# bs_prod.net
KiCad netlist of a schematic drawn in EAGLE
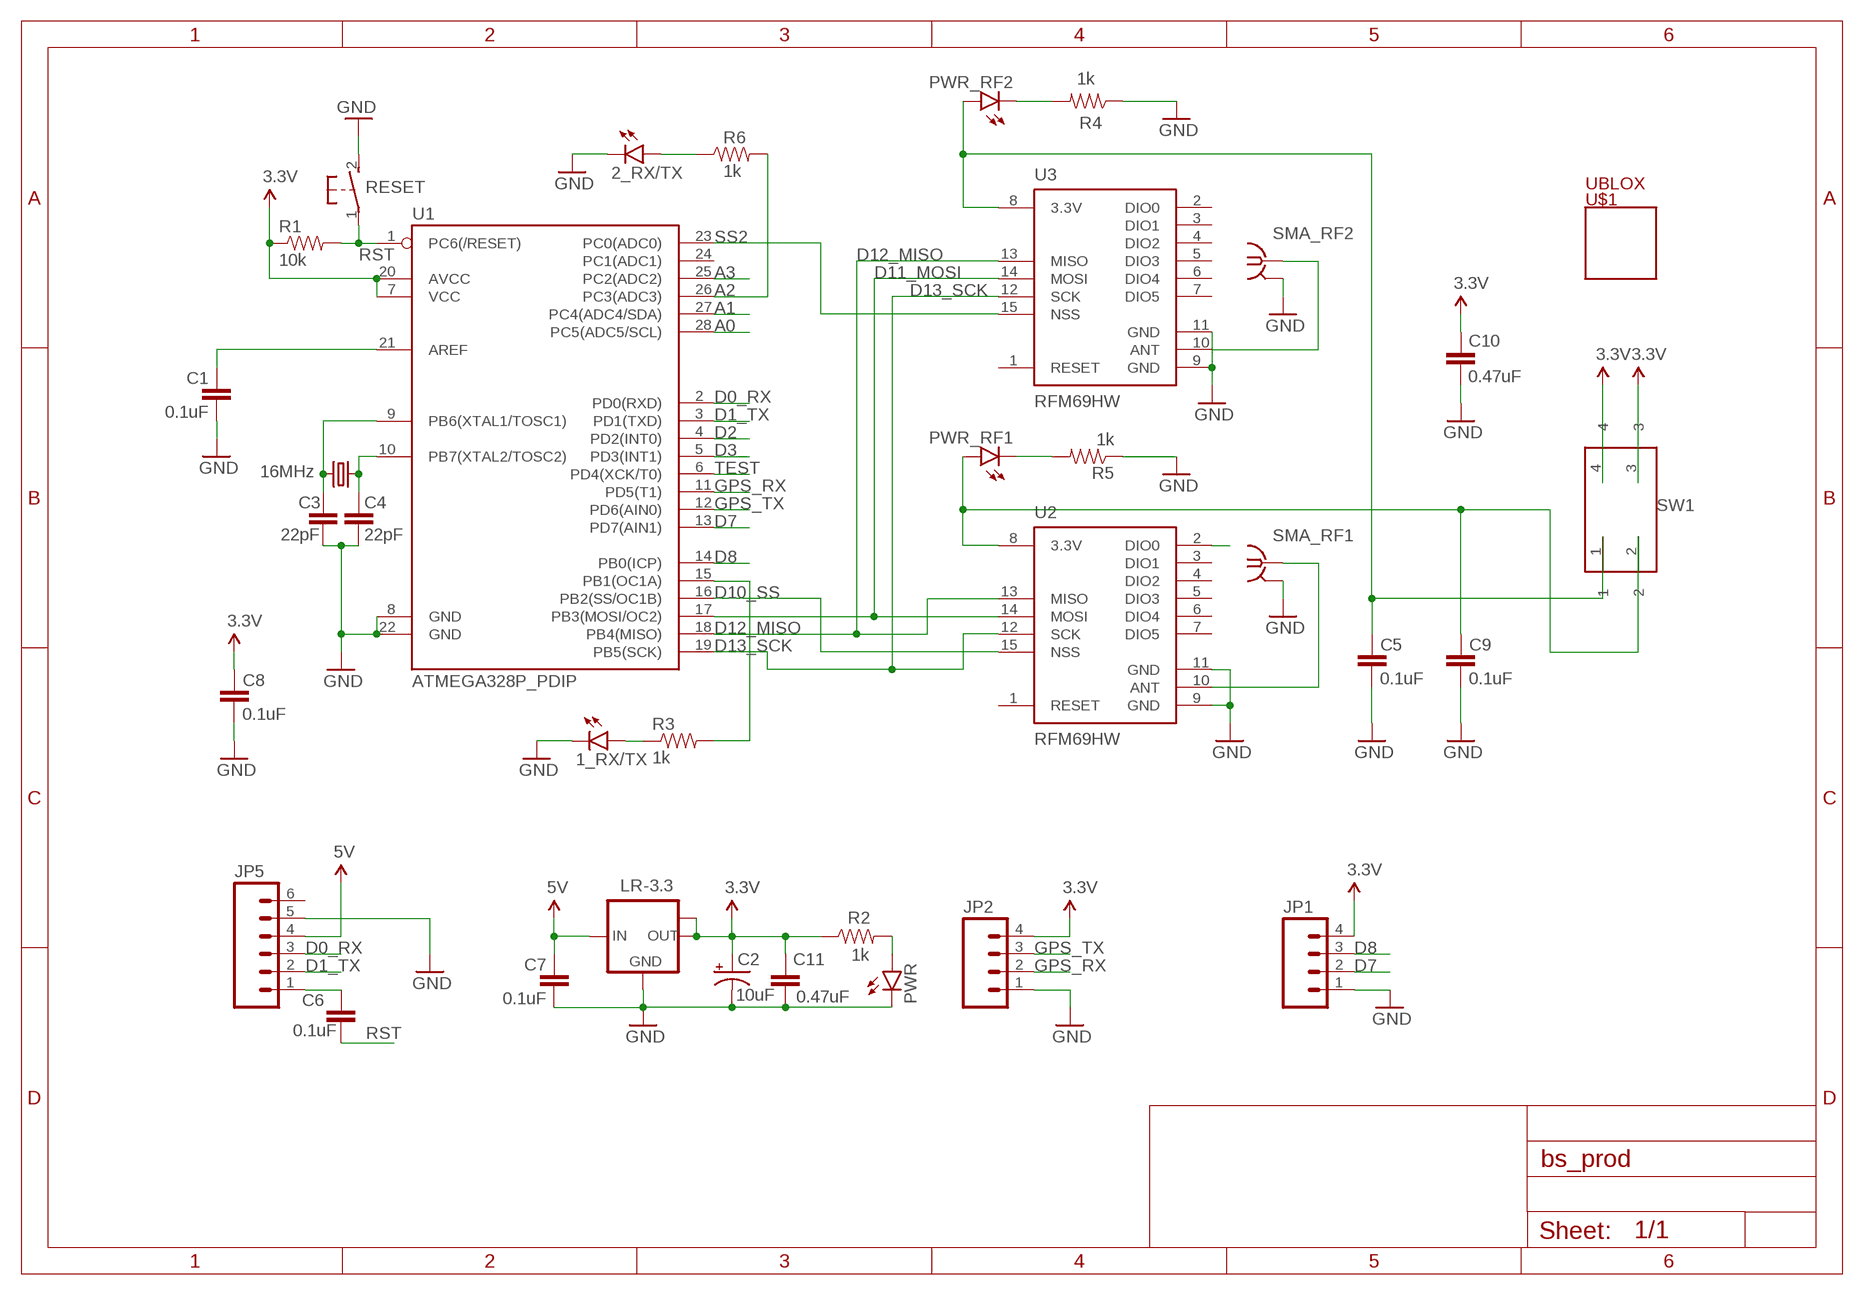
[diagram p0: schematic, sheet 1]

(export (version "E")
  (design (tool "Eeschema 10.0.6"))
  (components
    (comp (ref "1_RX/TX")
      (value "LED1206")
      (footprint "eagle-import:LED-1206")
      (libsource (lib "eagle-import") (part "LED1206"))
    )
    (comp (ref "2_RX/TX")
      (value "LED1206")
      (footprint "eagle-import:LED-1206")
      (libsource (lib "eagle-import") (part "LED1206"))
    )
    (comp (ref "C1")
      (value "0.1uF")
      (footprint "eagle-import:1206")
      (libsource (lib "eagle-import") (part "CAP1206"))
    )
    (comp (ref "C2")
      (value "10uF")
      (footprint "eagle-import:PANASONIC_C")
      (libsource (lib "eagle-import") (part "CAP_POLC"))
    )
    (comp (ref "C3")
      (value "22pF")
      (footprint "eagle-import:1206")
      (libsource (lib "eagle-import") (part "CAP1206"))
    )
    (comp (ref "C4")
      (value "22pF")
      (footprint "eagle-import:1206")
      (libsource (lib "eagle-import") (part "CAP1206"))
    )
    (comp (ref "C5")
      (value "0.1uF")
      (footprint "eagle-import:1206")
      (libsource (lib "eagle-import") (part "CAP1206"))
    )
    (comp (ref "C6")
      (value "0.1uF")
      (footprint "eagle-import:1206")
      (libsource (lib "eagle-import") (part "CAP1206"))
    )
    (comp (ref "C7")
      (value "0.1uF")
      (footprint "eagle-import:1206")
      (libsource (lib "eagle-import") (part "CAP1206"))
    )
    (comp (ref "C8")
      (value "0.1uF")
      (footprint "eagle-import:1206")
      (libsource (lib "eagle-import") (part "CAP1206"))
    )
    (comp (ref "C9")
      (value "0.1uF")
      (footprint "eagle-import:1206")
      (libsource (lib "eagle-import") (part "CAP1206"))
    )
    (comp (ref "C10")
      (value "0.47uF")
      (footprint "eagle-import:1206")
      (libsource (lib "eagle-import") (part "CAP1206"))
    )
    (comp (ref "C11")
      (value "0.47uF")
      (footprint "eagle-import:1206")
      (libsource (lib "eagle-import") (part "CAP1206"))
    )
    (comp (ref "JP1")
      (value "M04PTH")
      (footprint "eagle-import:1X04")
      (libsource (lib "eagle-import") (part "M04PTH"))
    )
    (comp (ref "JP2")
      (value "M04PTH")
      (footprint "eagle-import:1X04")
      (libsource (lib "eagle-import") (part "M04PTH"))
    )
    (comp (ref "JP5")
      (value "M06SIP")
      (footprint "eagle-import:1X06")
      (libsource (lib "eagle-import") (part "M06SIP"))
    )
    (comp (ref "LR-3.3")
      (value "LM1117IMPX-3.3")
      (footprint "eagle-import:SOT223")
      (libsource (lib "eagle-import") (part "LM1117IMPX-3.3"))
    )
    (comp (ref "PWR")
      (value "LED1206")
      (footprint "eagle-import:LED-1206")
      (libsource (lib "eagle-import") (part "LED1206"))
    )
    (comp (ref "PWR_RF1")
      (value "LED1206")
      (footprint "eagle-import:LED-1206")
      (libsource (lib "eagle-import") (part "LED1206"))
    )
    (comp (ref "PWR_RF2")
      (value "LED1206")
      (footprint "eagle-import:LED-1206")
      (libsource (lib "eagle-import") (part "LED1206"))
    )
    (comp (ref "R1")
      (value "10k")
      (footprint "eagle-import:1206")
      (libsource (lib "eagle-import") (part "RESISTOR1206"))
    )
    (comp (ref "R2")
      (value "1k")
      (footprint "eagle-import:1206")
      (libsource (lib "eagle-import") (part "RESISTOR1206"))
    )
    (comp (ref "R3")
      (value "1k")
      (footprint "eagle-import:1206")
      (libsource (lib "eagle-import") (part "RESISTOR1206"))
    )
    (comp (ref "R4")
      (value "1k")
      (footprint "eagle-import:1206")
      (libsource (lib "eagle-import") (part "RESISTOR1206"))
    )
    (comp (ref "R5")
      (value "1k")
      (footprint "eagle-import:1206")
      (libsource (lib "eagle-import") (part "RESISTOR1206"))
    )
    (comp (ref "R6")
      (value "1k")
      (footprint "eagle-import:1206")
      (libsource (lib "eagle-import") (part "RESISTOR1206"))
    )
    (comp (ref "RESET")
      (value "DTSM-3")
      (footprint "eagle-import:DTSM-3")
      (libsource (lib "eagle-import") (part "DTSM-3"))
    )
    (comp (ref "SMA_RF1")
      (value "BU-SMC-V")
      (footprint "eagle-import:BU-SMC-V")
      (libsource (lib "eagle-import") (part "BU-SMC-V"))
    )
    (comp (ref "SMA_RF2")
      (value "BU-SMC-V")
      (footprint "eagle-import:BU-SMC-V")
      (libsource (lib "eagle-import") (part "BU-SMC-V"))
    )
    (comp (ref "SW1")
      (value "418117270902")
      (footprint "eagle-import:418117270902")
      (libsource (lib "eagle-import") (part "418117270902"))
    )
    (comp (ref "U$1")
      (value "UBLOX")
      (footprint "eagle-import:UBLOX")
      (libsource (lib "eagle-import") (part "UBLOX"))
    )
    (comp (ref "U1")
      (value "ATMEGA328P_PDIP")
      (footprint "eagle-import:DIL28-3")
      (libsource (lib "eagle-import") (part "ATMEGA328P_PDIP"))
    )
    (comp (ref "U2")
      (value "RFM69HW")
      (footprint "eagle-import:RFM69W-XXXS2")
      (libsource (lib "eagle-import") (part "RFM69HW"))
    )
    (comp (ref "U3")
      (value "RFM69HW")
      (footprint "eagle-import:RFM69W-XXXS2")
      (libsource (lib "eagle-import") (part "RFM69HW"))
    )
    (comp (ref "Y1")
      (value "16MHz")
      (footprint "eagle-import:HC49UP")
      (libsource (lib "eagle-import") (part "CRYSTALSMD"))
    )
  )
  (nets
    (net (code "1") (name "/A0") (class "Default")
      (node (ref "U1") (pin "28") (pinfunction "PC5(ADC5/SCL)_28") (pintype "bidirectional"))
    )
    (net (code "2") (name "/A1") (class "Default")
      (node (ref "U1") (pin "27") (pinfunction "PC4(ADC4/SDA)_27") (pintype "bidirectional"))
    )
    (net (code "3") (name "/A2") (class "Default")
      (node (ref "R6") (pin "2") (pinfunction "2_2") (pintype "passive"))
      (node (ref "U1") (pin "26") (pinfunction "PC3(ADC3)_26") (pintype "bidirectional"))
    )
    (net (code "4") (name "/A3") (class "Default")
      (node (ref "U1") (pin "25") (pinfunction "PC2(ADC2)_25") (pintype "bidirectional"))
    )
    (net (code "5") (name "/D0_RX") (class "Default")
      (node (ref "JP5") (pin "3") (pinfunction "3_3") (pintype "passive"))
      (node (ref "U1") (pin "2") (pinfunction "PD0(RXD)_2") (pintype "bidirectional"))
    )
    (net (code "6") (name "/D1_TX") (class "Default")
      (node (ref "JP5") (pin "2") (pinfunction "2_2") (pintype "passive"))
      (node (ref "U1") (pin "3") (pinfunction "PD1(TXD)_3") (pintype "bidirectional"))
    )
    (net (code "7") (name "/D2") (class "Default")
      (node (ref "U1") (pin "4") (pinfunction "PD2(INT0)_4") (pintype "bidirectional"))
    )
    (net (code "8") (name "/D3") (class "Default")
      (node (ref "U1") (pin "5") (pinfunction "PD3(INT1)_5") (pintype "bidirectional"))
    )
    (net (code "9") (name "/D7") (class "Default")
      (node (ref "JP1") (pin "2") (pinfunction "2_2") (pintype "passive"))
      (node (ref "U1") (pin "13") (pinfunction "PD7(AIN1)_13") (pintype "bidirectional"))
    )
    (net (code "10") (name "/D8") (class "Default")
      (node (ref "JP1") (pin "3") (pinfunction "3_3") (pintype "passive"))
      (node (ref "U1") (pin "14") (pinfunction "PB0(ICP)_14") (pintype "bidirectional"))
    )
    (net (code "11") (name "/D10_SS") (class "Default")
      (node (ref "U1") (pin "16") (pinfunction "PB2(SS/OC1B)_16") (pintype "bidirectional"))
      (node (ref "U2") (pin "15") (pinfunction "NSS_15") (pintype "input"))
    )
    (net (code "12") (name "/D11_MOSI") (class "Default")
      (node (ref "U1") (pin "17") (pinfunction "PB3(MOSI/OC2)_17") (pintype "bidirectional"))
      (node (ref "U2") (pin "14") (pinfunction "MOSI_14") (pintype "input"))
      (node (ref "U3") (pin "14") (pinfunction "MOSI_14") (pintype "input"))
    )
    (net (code "13") (name "/D12_MISO") (class "Default")
      (node (ref "U1") (pin "18") (pinfunction "PB4(MISO)_18") (pintype "bidirectional"))
      (node (ref "U2") (pin "13") (pinfunction "MISO_13") (pintype "bidirectional"))
      (node (ref "U3") (pin "13") (pinfunction "MISO_13") (pintype "bidirectional"))
    )
    (net (code "14") (name "/D13_SCK") (class "Default")
      (node (ref "U1") (pin "19") (pinfunction "PB5(SCK)_19") (pintype "bidirectional"))
      (node (ref "U2") (pin "12") (pinfunction "SCK_12") (pintype "input"))
      (node (ref "U3") (pin "12") (pinfunction "SCK_12") (pintype "input"))
    )
    (net (code "15") (name "/GPS_RX") (class "Default")
      (node (ref "JP2") (pin "2") (pinfunction "2_2") (pintype "passive"))
      (node (ref "U1") (pin "11") (pinfunction "PD5(T1)_11") (pintype "bidirectional"))
    )
    (net (code "16") (name "/GPS_TX") (class "Default")
      (node (ref "JP2") (pin "3") (pinfunction "3_3") (pintype "passive"))
      (node (ref "U1") (pin "12") (pinfunction "PD6(AIN0)_12") (pintype "bidirectional"))
    )
    (net (code "17") (name "/RST") (class "Default")
      (node (ref "C6") (pin "2") (pinfunction "2_2") (pintype "passive"))
      (node (ref "R1") (pin "2") (pinfunction "2_2") (pintype "passive"))
      (node (ref "RESET") (pin "1") (pinfunction "1_1") (pintype "passive"))
      (node (ref "U1") (pin "1") (pinfunction "PC6(/RESET)_1") (pintype "bidirectional"))
    )
    (net (code "18") (name "/SS2") (class "Default")
      (node (ref "U1") (pin "23") (pinfunction "PC0(ADC0)_23") (pintype "bidirectional"))
      (node (ref "U3") (pin "15") (pinfunction "NSS_15") (pintype "input"))
    )
    (net (code "19") (name "/TEST") (class "Default")
      (node (ref "U1") (pin "6") (pinfunction "PD4(XCK/T0)_6") (pintype "bidirectional"))
    )
    (net (code "20") (name "3.3V") (class "Default")
      (node (ref "C10") (pin "1") (pinfunction "1_1") (pintype "passive"))
      (node (ref "C11") (pin "1") (pinfunction "1_1") (pintype "passive"))
      (node (ref "C2") (pin "+") (pinfunction "+_+") (pintype "passive"))
      (node (ref "C8") (pin "1") (pinfunction "1_1") (pintype "passive"))
      (node (ref "JP1") (pin "4") (pinfunction "4_4") (pintype "passive"))
      (node (ref "JP2") (pin "4") (pinfunction "4_4") (pintype "passive"))
      (node (ref "LR-3.3") (pin "2") (pinfunction "OUT_2") (pintype "passive"))
      (node (ref "LR-3.3") (pin "TAB") (pinfunction "OUT1_TAB") (pintype "passive"))
      (node (ref "R1") (pin "1") (pinfunction "1_1") (pintype "passive"))
      (node (ref "R2") (pin "1") (pinfunction "1_1") (pintype "passive"))
      (node (ref "SW1") (pin "3") (pinfunction "3_3") (pintype "bidirectional"))
      (node (ref "SW1") (pin "4") (pinfunction "4_4") (pintype "bidirectional"))
      (node (ref "U1") (pin "20") (pinfunction "AVCC_20") (pintype "bidirectional"))
      (node (ref "U1") (pin "7") (pinfunction "VCC_7") (pintype "bidirectional"))
    )
    (net (code "21") (name "5V") (class "Default")
      (node (ref "C7") (pin "1") (pinfunction "1_1") (pintype "passive"))
      (node (ref "JP5") (pin "4") (pinfunction "4_4") (pintype "passive"))
      (node (ref "LR-3.3") (pin "3") (pinfunction "IN_3") (pintype "input"))
    )
    (net (code "22") (name "GND") (class "Default")
      (node (ref "1_RX/TX") (pin "C") (pinfunction "C_C") (pintype "passive"))
      (node (ref "2_RX/TX") (pin "C") (pinfunction "C_C") (pintype "passive"))
      (node (ref "C1") (pin "2") (pinfunction "2_2") (pintype "passive"))
      (node (ref "C10") (pin "2") (pinfunction "2_2") (pintype "passive"))
      (node (ref "C11") (pin "2") (pinfunction "2_2") (pintype "passive"))
      (node (ref "C2") (pin "-") (pinfunction "-_-") (pintype "passive"))
      (node (ref "C3") (pin "2") (pinfunction "2_2") (pintype "passive"))
      (node (ref "C4") (pin "2") (pinfunction "2_2") (pintype "passive"))
      (node (ref "C5") (pin "2") (pinfunction "2_2") (pintype "passive"))
      (node (ref "C7") (pin "2") (pinfunction "2_2") (pintype "passive"))
      (node (ref "C8") (pin "2") (pinfunction "2_2") (pintype "passive"))
      (node (ref "C9") (pin "2") (pinfunction "2_2") (pintype "passive"))
      (node (ref "JP1") (pin "1") (pinfunction "1_1") (pintype "passive"))
      (node (ref "JP2") (pin "1") (pinfunction "1_1") (pintype "passive"))
      (node (ref "JP5") (pin "5") (pinfunction "5_5") (pintype "passive"))
      (node (ref "LR-3.3") (pin "1") (pinfunction "GND_1") (pintype "input"))
      (node (ref "PWR") (pin "C") (pinfunction "C_C") (pintype "passive"))
      (node (ref "R4") (pin "1") (pinfunction "1_1") (pintype "passive"))
      (node (ref "R5") (pin "1") (pinfunction "1_1") (pintype "passive"))
      (node (ref "RESET") (pin "2") (pinfunction "2_2") (pintype "passive"))
      (node (ref "SMA_RF1") (pin "2") (pinfunction "2_2") (pintype "passive"))
      (node (ref "SMA_RF1") (pin "3") (pinfunction "2_3") (pintype "passive"))
      (node (ref "SMA_RF1") (pin "4") (pinfunction "2_4") (pintype "passive"))
      (node (ref "SMA_RF1") (pin "5") (pinfunction "2_5") (pintype "passive"))
      (node (ref "SMA_RF2") (pin "2") (pinfunction "2_2") (pintype "passive"))
      (node (ref "SMA_RF2") (pin "3") (pinfunction "2_3") (pintype "passive"))
      (node (ref "SMA_RF2") (pin "4") (pinfunction "2_4") (pintype "passive"))
      (node (ref "SMA_RF2") (pin "5") (pinfunction "2_5") (pintype "passive"))
      (node (ref "U1") (pin "22") (pinfunction "GND_22") (pintype "bidirectional"))
      (node (ref "U1") (pin "8") (pinfunction "GND_8") (pintype "bidirectional"))
      (node (ref "U2") (pin "11") (pinfunction "GND_11") (pintype "power_in"))
      (node (ref "U2") (pin "9") (pinfunction "GND_9") (pintype "power_in"))
      (node (ref "U3") (pin "11") (pinfunction "GND_11") (pintype "power_in"))
      (node (ref "U3") (pin "9") (pinfunction "GND_9") (pintype "power_in"))
    )
    (net (code "23") (name "Net-(1_RX/TX-PadA)") (class "Default")
      (node (ref "1_RX/TX") (pin "A") (pinfunction "A_A") (pintype "passive"))
      (node (ref "R3") (pin "1") (pinfunction "1_1") (pintype "passive"))
    )
    (net (code "24") (name "Net-(2_RX/TX-PadA)") (class "Default")
      (node (ref "2_RX/TX") (pin "A") (pinfunction "A_A") (pintype "passive"))
      (node (ref "R6") (pin "1") (pinfunction "1_1") (pintype "passive"))
    )
    (net (code "25") (name "Net-(C6-Pad1)") (class "Default")
      (node (ref "C6") (pin "1") (pinfunction "1_1") (pintype "passive"))
      (node (ref "JP5") (pin "1") (pinfunction "1_1") (pintype "passive"))
    )
    (net (code "26") (name "Net-(PWR-PadA)") (class "Default")
      (node (ref "PWR") (pin "A") (pinfunction "A_A") (pintype "passive"))
      (node (ref "R2") (pin "2") (pinfunction "2_2") (pintype "passive"))
    )
    (net (code "27") (name "Net-(PWR_RF1-PadC)") (class "Default")
      (node (ref "PWR_RF1") (pin "C") (pinfunction "C_C") (pintype "passive"))
      (node (ref "R5") (pin "2") (pinfunction "2_2") (pintype "passive"))
    )
    (net (code "28") (name "Net-(PWR_RF2-PadC)") (class "Default")
      (node (ref "PWR_RF2") (pin "C") (pinfunction "C_C") (pintype "passive"))
      (node (ref "R4") (pin "2") (pinfunction "2_2") (pintype "passive"))
    )
    (net (code "29") (name "Net-(U1-AREF)") (class "Default")
      (node (ref "C1") (pin "1") (pinfunction "1_1") (pintype "passive"))
      (node (ref "U1") (pin "21") (pinfunction "AREF_21") (pintype "bidirectional"))
    )
    (net (code "30") (name "Net-(U1-PB1(OC1A))") (class "Default")
      (node (ref "R3") (pin "2") (pinfunction "2_2") (pintype "passive"))
      (node (ref "U1") (pin "15") (pinfunction "PB1(OC1A)_15") (pintype "bidirectional"))
    )
    (net (code "31") (name "Net-(U1-PB6(XTAL1{slash}TOSC1))") (class "Default")
      (node (ref "C3") (pin "1") (pinfunction "1_1") (pintype "passive"))
      (node (ref "U1") (pin "9") (pinfunction "PB6(XTAL1/TOSC1)_9") (pintype "bidirectional"))
      (node (ref "Y1") (pin "2") (pinfunction "2_2") (pintype "passive"))
    )
    (net (code "32") (name "Net-(U1-PB7(XTAL2{slash}TOSC2))") (class "Default")
      (node (ref "C4") (pin "1") (pinfunction "1_1") (pintype "passive"))
      (node (ref "U1") (pin "10") (pinfunction "PB7(XTAL2/TOSC2)_10") (pintype "bidirectional"))
      (node (ref "Y1") (pin "1") (pinfunction "1_1") (pintype "passive"))
    )
    (net (code "33") (name "Net-(U2-3.3V)") (class "Default")
      (node (ref "C9") (pin "1") (pinfunction "1_1") (pintype "passive"))
      (node (ref "PWR_RF1") (pin "A") (pinfunction "A_A") (pintype "passive"))
      (node (ref "SW1") (pin "2") (pinfunction "2_2") (pintype "bidirectional"))
      (node (ref "U2") (pin "8") (pinfunction "3.3V_8") (pintype "power_in"))
    )
    (net (code "34") (name "Net-(U2-ANT)") (class "Default")
      (node (ref "SMA_RF1") (pin "1") (pinfunction "1_1") (pintype "passive"))
      (node (ref "U2") (pin "10") (pinfunction "ANT_10") (pintype "passive"))
    )
    (net (code "35") (name "Net-(U3-3.3V)") (class "Default")
      (node (ref "C5") (pin "1") (pinfunction "1_1") (pintype "passive"))
      (node (ref "PWR_RF2") (pin "A") (pinfunction "A_A") (pintype "passive"))
      (node (ref "SW1") (pin "1") (pinfunction "1_1") (pintype "bidirectional"))
      (node (ref "U3") (pin "8") (pinfunction "3.3V_8") (pintype "power_in"))
    )
    (net (code "36") (name "Net-(U3-ANT)") (class "Default")
      (node (ref "SMA_RF2") (pin "1") (pinfunction "1_1") (pintype "passive"))
      (node (ref "U3") (pin "10") (pinfunction "ANT_10") (pintype "passive"))
    )
    (net (code "37") (name "unconnected-(JP5-Pad6)") (class "Default")
      (node (ref "JP5") (pin "6") (pinfunction "6_6") (pintype "passive"))
    )
    (net (code "38") (name "unconnected-(U1-PC1(ADC1)-Pad24)") (class "Default")
      (node (ref "U1") (pin "24") (pinfunction "PC1(ADC1)_24") (pintype "bidirectional"))
    )
    (net (code "39") (name "unconnected-(U2-DIO0-Pad2)") (class "Default")
      (node (ref "U2") (pin "2") (pinfunction "DIO0_2") (pintype "bidirectional"))
    )
    (net (code "40") (name "unconnected-(U2-DIO1-Pad3)") (class "Default")
      (node (ref "U2") (pin "3") (pinfunction "DIO1_3") (pintype "bidirectional"))
    )
    (net (code "41") (name "unconnected-(U2-DIO2-Pad4)") (class "Default")
      (node (ref "U2") (pin "4") (pinfunction "DIO2_4") (pintype "bidirectional"))
    )
    (net (code "42") (name "unconnected-(U2-DIO3-Pad5)") (class "Default")
      (node (ref "U2") (pin "5") (pinfunction "DIO3_5") (pintype "bidirectional"))
    )
    (net (code "43") (name "unconnected-(U2-DIO4-Pad6)") (class "Default")
      (node (ref "U2") (pin "6") (pinfunction "DIO4_6") (pintype "bidirectional"))
    )
    (net (code "44") (name "unconnected-(U2-DIO5-Pad7)") (class "Default")
      (node (ref "U2") (pin "7") (pinfunction "DIO5_7") (pintype "bidirectional"))
    )
    (net (code "45") (name "unconnected-(U2-RESET-Pad1)") (class "Default")
      (node (ref "U2") (pin "1") (pinfunction "RESET_1") (pintype "input"))
    )
    (net (code "46") (name "unconnected-(U3-DIO0-Pad2)") (class "Default")
      (node (ref "U3") (pin "2") (pinfunction "DIO0_2") (pintype "bidirectional"))
    )
    (net (code "47") (name "unconnected-(U3-DIO1-Pad3)") (class "Default")
      (node (ref "U3") (pin "3") (pinfunction "DIO1_3") (pintype "bidirectional"))
    )
    (net (code "48") (name "unconnected-(U3-DIO2-Pad4)") (class "Default")
      (node (ref "U3") (pin "4") (pinfunction "DIO2_4") (pintype "bidirectional"))
    )
    (net (code "49") (name "unconnected-(U3-DIO3-Pad5)") (class "Default")
      (node (ref "U3") (pin "5") (pinfunction "DIO3_5") (pintype "bidirectional"))
    )
    (net (code "50") (name "unconnected-(U3-DIO4-Pad6)") (class "Default")
      (node (ref "U3") (pin "6") (pinfunction "DIO4_6") (pintype "bidirectional"))
    )
    (net (code "51") (name "unconnected-(U3-DIO5-Pad7)") (class "Default")
      (node (ref "U3") (pin "7") (pinfunction "DIO5_7") (pintype "bidirectional"))
    )
    (net (code "52") (name "unconnected-(U3-RESET-Pad1)") (class "Default")
      (node (ref "U3") (pin "1") (pinfunction "RESET_1") (pintype "input"))
    )
  )
)
